# stm32f4_sd.net
KiCad netlist of a schematic drawn in EAGLE
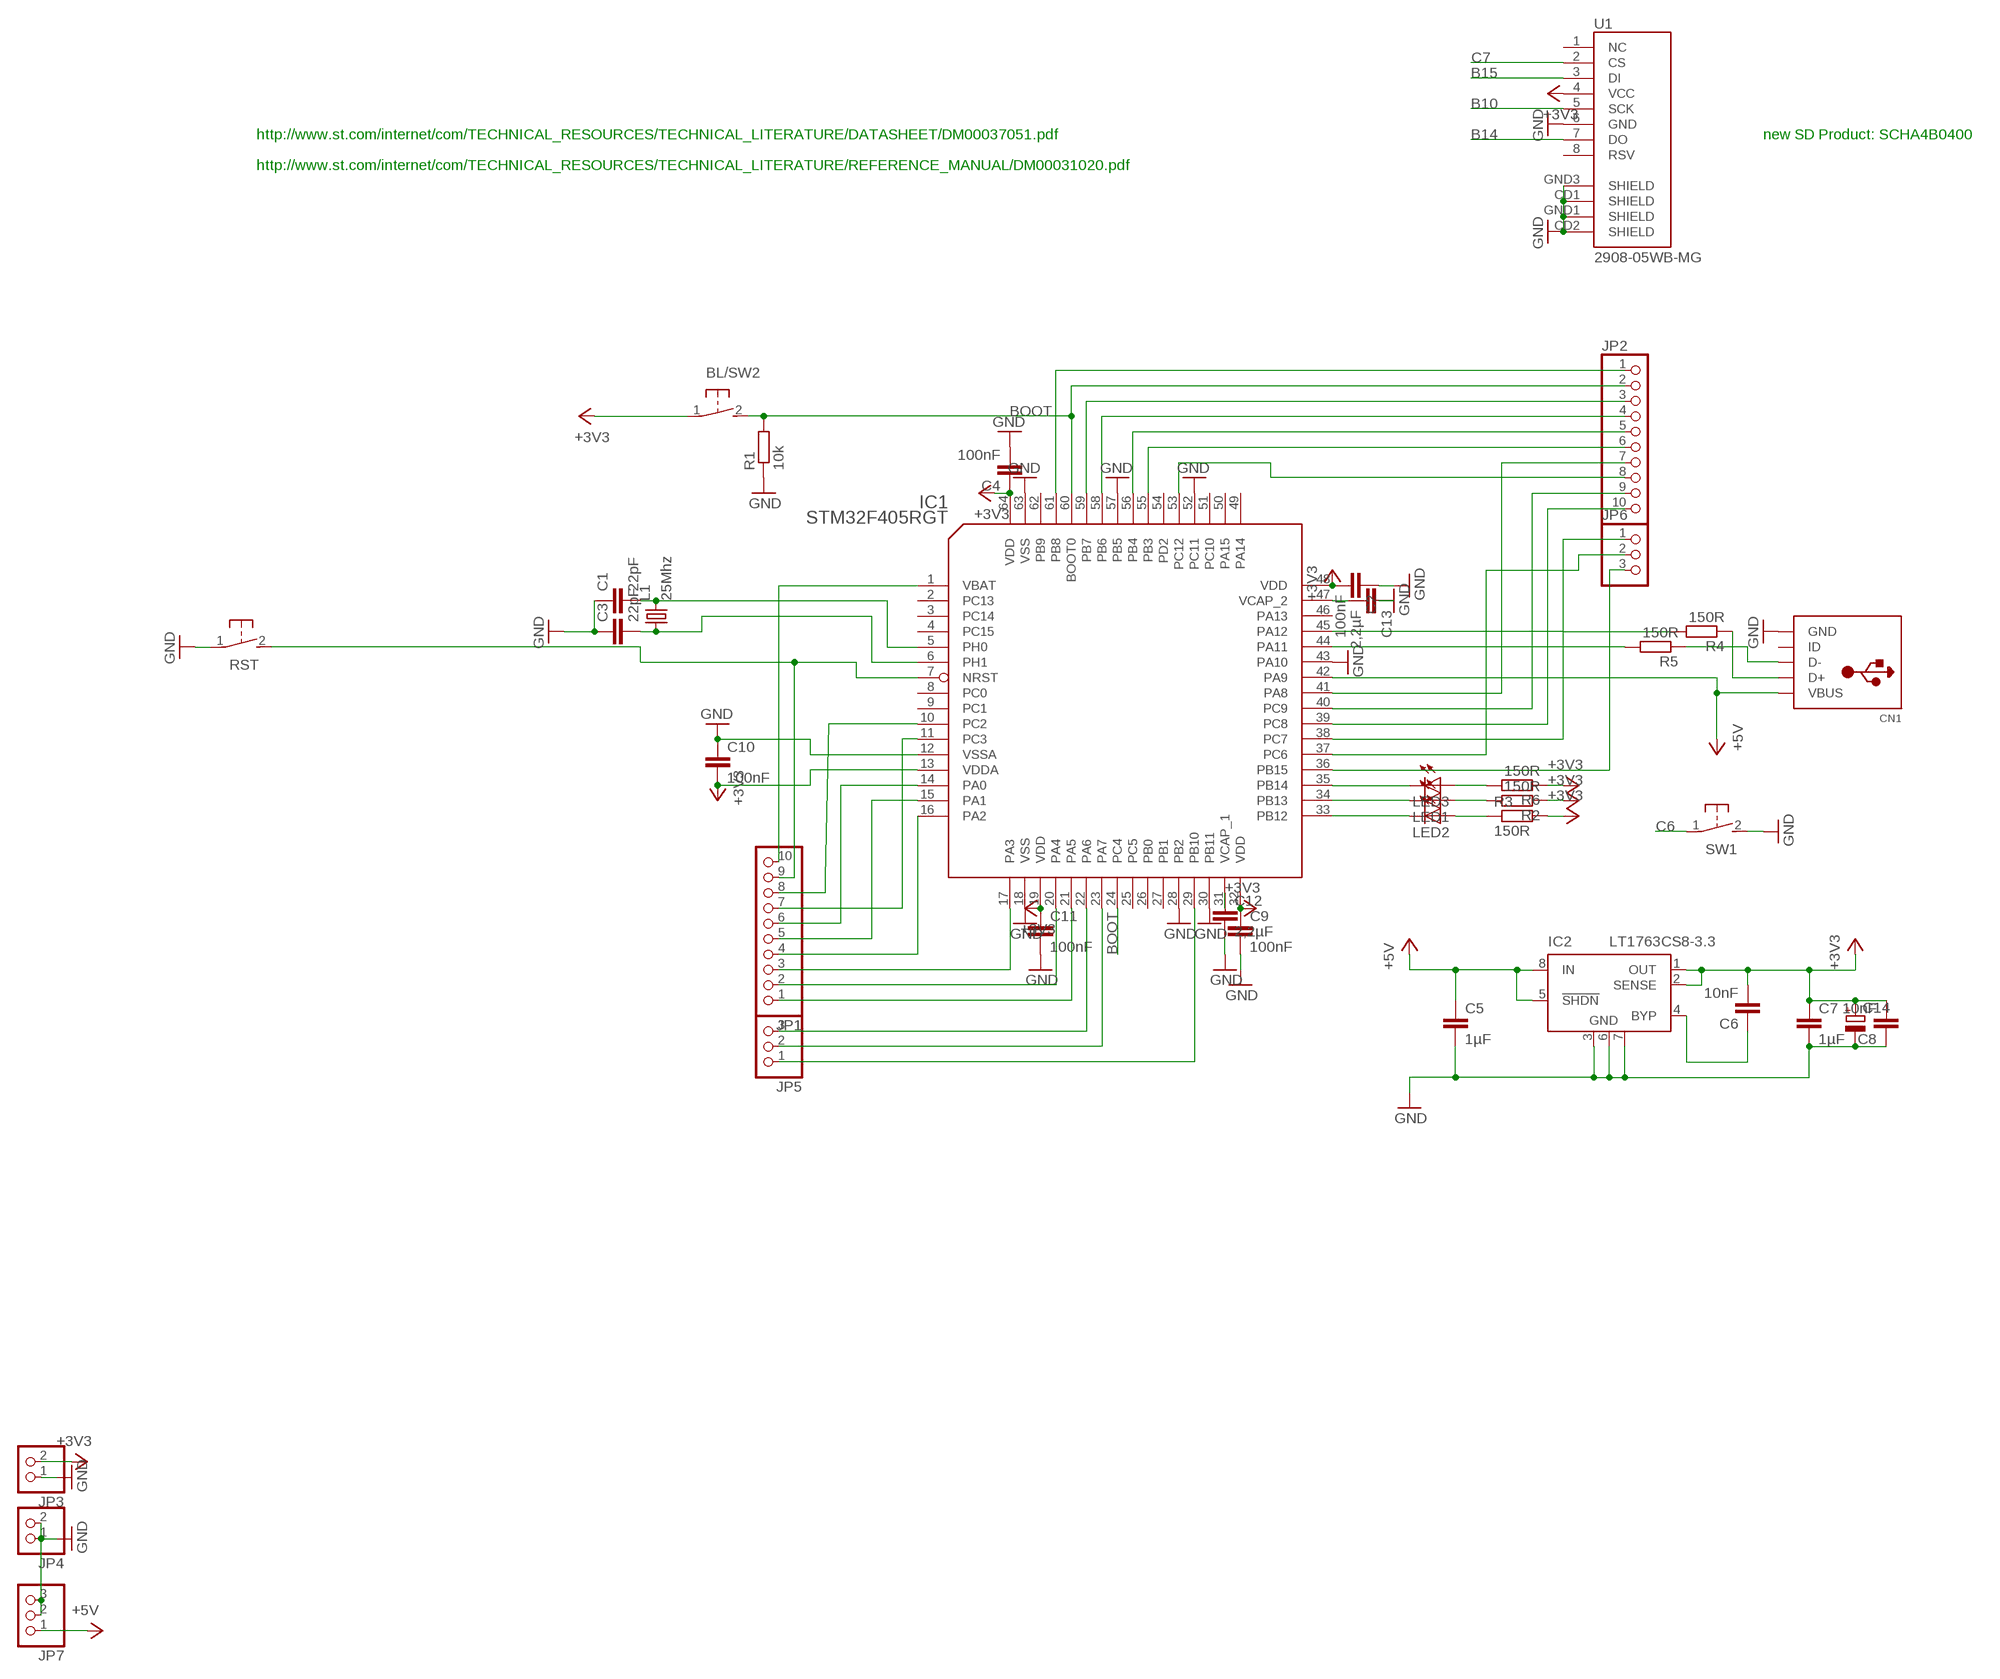
[diagram p0: schematic, sheet 1]

(export (version "E")
  (design (tool "Eeschema 10.0.6"))
  (components
    (comp (ref "BL/SW2")
      (value "SWITCH_MCTAEF")
      (footprint "eagle-import:SWITCH_MCTAEF")
      (libsource (lib "eagle-import") (part "SWITCH_MCTAEF"))
    )
    (comp (ref "C1")
      (value "22pF")
      (footprint "eagle-import:C0402")
      (libsource (lib "eagle-import") (part "C-EUC0402"))
    )
    (comp (ref "C2")
      (value "100nF")
      (footprint "eagle-import:C0402")
      (libsource (lib "eagle-import") (part "C-EUC0402"))
    )
    (comp (ref "C3")
      (value "22pF")
      (footprint "eagle-import:C0402")
      (libsource (lib "eagle-import") (part "C-EUC0402"))
    )
    (comp (ref "C4")
      (value "100nF")
      (footprint "eagle-import:C0402")
      (libsource (lib "eagle-import") (part "C-EUC0402"))
    )
    (comp (ref "C5")
      (value "1µF")
      (footprint "eagle-import:0805")
      (libsource (lib "eagle-import") (part "CAP0805"))
    )
    (comp (ref "C6")
      (value "10nF")
      (footprint "eagle-import:C0402")
      (libsource (lib "eagle-import") (part "C-EUC0402"))
    )
    (comp (ref "C7")
      (value "1µF")
      (footprint "eagle-import:0805")
      (libsource (lib "eagle-import") (part "CAP0805"))
    )
    (comp (ref "C8")
      (value "10nF")
      (footprint "eagle-import:C0402")
      (libsource (lib "eagle-import") (part "C-EUC0402"))
    )
    (comp (ref "C9")
      (value "100nF")
      (footprint "eagle-import:C0402")
      (libsource (lib "eagle-import") (part "C-EUC0402"))
    )
    (comp (ref "C10")
      (value "100nF")
      (footprint "eagle-import:C0402")
      (libsource (lib "eagle-import") (part "C-EUC0402"))
    )
    (comp (ref "C11")
      (value "100nF")
      (footprint "eagle-import:C0402")
      (libsource (lib "eagle-import") (part "C-EUC0402"))
    )
    (comp (ref "C12")
      (value "2,2µF")
      (footprint "eagle-import:0805")
      (libsource (lib "eagle-import") (part "CAP0805"))
    )
    (comp (ref "C13")
      (value "2,2µF")
      (footprint "eagle-import:0805")
      (libsource (lib "eagle-import") (part "CAP0805"))
    )
    (comp (ref "C14")
      (value "CPOL-EUSMCA")
      (footprint "eagle-import:SMC_A")
      (libsource (lib "eagle-import") (part "CPOL-EUSMCA"))
    )
    (comp (ref "CN1")
      (value "USBMINIB")
      (footprint "eagle-import:USB-MINIB")
      (libsource (lib "eagle-import") (part "USBMINIB"))
    )
    (comp (ref "IC1")
      (value "STM32F405RGT")
      (footprint "eagle-import:LQFP64")
      (libsource (lib "eagle-import") (part "STM32F405RTG"))
    )
    (comp (ref "IC2")
      (value "LT1763CS8-3.3")
      (footprint "eagle-import:SOIC8")
      (libsource (lib "eagle-import") (part "LT1763CS8-3.3"))
    )
    (comp (ref "JP1")
      (value "PINHD-1X10_2.54")
      (footprint "eagle-import:1X10")
      (libsource (lib "eagle-import") (part "PINHD-1X10_2.54"))
    )
    (comp (ref "JP2")
      (value "PINHD-1X10_2.54")
      (footprint "eagle-import:1X10")
      (libsource (lib "eagle-import") (part "PINHD-1X10_2.54"))
    )
    (comp (ref "JP3")
      (value "PINHD-1X02_2.54")
      (footprint "eagle-import:1X02")
      (libsource (lib "eagle-import") (part "PINHD-1X02_2.54"))
    )
    (comp (ref "JP4")
      (value "PINHD-1X02_2.54")
      (footprint "eagle-import:1X02")
      (libsource (lib "eagle-import") (part "PINHD-1X02_2.54"))
    )
    (comp (ref "JP5")
      (value "PINHD-1X03_2.54")
      (footprint "eagle-import:1X03")
      (libsource (lib "eagle-import") (part "PINHD-1X03_2.54"))
    )
    (comp (ref "JP6")
      (value "PINHD-1X03_2.54")
      (footprint "eagle-import:1X03")
      (libsource (lib "eagle-import") (part "PINHD-1X03_2.54"))
    )
    (comp (ref "JP7")
      (value "PINHD-1X03_2.54")
      (footprint "eagle-import:1X03")
      (libsource (lib "eagle-import") (part "PINHD-1X03_2.54"))
    )
    (comp (ref "L1")
      (value "25Mhz")
      (footprint "eagle-import:X22")
      (libsource (lib "eagle-import") (part "X22-OSCILLATOR"))
    )
    (comp (ref "LED1")
      (value "LED0603")
      (footprint "eagle-import:LED-0603")
      (libsource (lib "eagle-import") (part "LED0603"))
    )
    (comp (ref "LED2")
      (value "LED0603")
      (footprint "eagle-import:LED-0603")
      (libsource (lib "eagle-import") (part "LED0603"))
    )
    (comp (ref "LED3")
      (value "LED0603")
      (footprint "eagle-import:LED-0603")
      (libsource (lib "eagle-import") (part "LED0603"))
    )
    (comp (ref "R1")
      (value "10k")
      (footprint "eagle-import:R0402")
      (libsource (lib "eagle-import") (part "R-EU_R0402"))
    )
    (comp (ref "R2")
      (value "150R")
      (footprint "eagle-import:R0402")
      (libsource (lib "eagle-import") (part "R-EU_R0402"))
    )
    (comp (ref "R3")
      (value "150R")
      (footprint "eagle-import:R0402")
      (libsource (lib "eagle-import") (part "R-EU_R0402"))
    )
    (comp (ref "R4")
      (value "150R")
      (footprint "eagle-import:R0402")
      (libsource (lib "eagle-import") (part "R-EU_R0402"))
    )
    (comp (ref "R5")
      (value "150R")
      (footprint "eagle-import:R0402")
      (libsource (lib "eagle-import") (part "R-EU_R0402"))
    )
    (comp (ref "R6")
      (value "150R")
      (footprint "eagle-import:R0402")
      (libsource (lib "eagle-import") (part "R-EU_R0402"))
    )
    (comp (ref "RST")
      (value "SWITCH_MCTAEF")
      (footprint "eagle-import:SWITCH_MCTAEF")
      (libsource (lib "eagle-import") (part "SWITCH_MCTAEF"))
    )
    (comp (ref "SW1")
      (value "SWITCH_MCTAEF")
      (footprint "eagle-import:SWITCH_MCTAEF")
      (libsource (lib "eagle-import") (part "SWITCH_MCTAEF"))
    )
    (comp (ref "U1")
      (value "2908-05WB-MG")
      (footprint "eagle-import:MICRO-SD-SOCKET-PP")
      (libsource (lib "eagle-import") (part "USD-SOCKETNEW"))
    )
  )
  (nets
    (net (code "1") (name "+3V3") (class "Default")
      (node (ref "BL/SW2") (pin "1") (pinfunction "1_1") (pintype "passive"))
      (node (ref "C10") (pin "2") (pinfunction "2_2") (pintype "passive"))
      (node (ref "C11") (pin "1") (pinfunction "1_1") (pintype "passive"))
      (node (ref "C14") (pin "+") (pinfunction "+_+") (pintype "passive"))
      (node (ref "C2") (pin "2") (pinfunction "2_2") (pintype "passive"))
      (node (ref "C4") (pin "1") (pinfunction "1_1") (pintype "passive"))
      (node (ref "C6") (pin "2") (pinfunction "2_2") (pintype "passive"))
      (node (ref "C7") (pin "1") (pinfunction "1_1") (pintype "passive"))
      (node (ref "C8") (pin "2") (pinfunction "2_2") (pintype "passive"))
      (node (ref "C9") (pin "1") (pinfunction "1_1") (pintype "passive"))
      (node (ref "IC1") (pin "13") (pinfunction "VDDA_13") (pintype "power_in"))
      (node (ref "IC1") (pin "19") (pinfunction "VDD_19") (pintype "power_in"))
      (node (ref "IC1") (pin "32") (pinfunction "VDD_32") (pintype "power_in"))
      (node (ref "IC1") (pin "48") (pinfunction "VDD_48") (pintype "power_in"))
      (node (ref "IC1") (pin "64") (pinfunction "VDD_64") (pintype "power_in"))
      (node (ref "IC2") (pin "1") (pinfunction "OUT_1") (pintype "passive"))
      (node (ref "IC2") (pin "2") (pinfunction "SENSE_2") (pintype "input"))
      (node (ref "JP3") (pin "2") (pinfunction "2_2") (pintype "passive"))
      (node (ref "R2") (pin "1") (pinfunction "1_1") (pintype "passive"))
      (node (ref "R3") (pin "2") (pinfunction "2_2") (pintype "passive"))
      (node (ref "R6") (pin "1") (pinfunction "1_1") (pintype "passive"))
      (node (ref "U1") (pin "4") (pinfunction "VCC_4") (pintype "bidirectional"))
    )
    (net (code "2") (name "+5V") (class "Default")
      (node (ref "C5") (pin "1") (pinfunction "1_1") (pintype "passive"))
      (node (ref "CN1") (pin "VBUS") (pinfunction "VBUS_VBUS") (pintype "power_in"))
      (node (ref "IC1") (pin "42") (pinfunction "PA9_42") (pintype "bidirectional"))
      (node (ref "IC2") (pin "5") (pinfunction "~{SHDN}_5") (pintype "input"))
      (node (ref "IC2") (pin "8") (pinfunction "IN_8") (pintype "input"))
      (node (ref "JP7") (pin "1") (pinfunction "1_1") (pintype "passive"))
    )
    (net (code "3") (name "/B10") (class "Default")
      (node (ref "IC1") (pin "29") (pinfunction "PB10_29") (pintype "bidirectional"))
      (node (ref "JP5") (pin "1") (pinfunction "1_1") (pintype "passive"))
      (node (ref "U1") (pin "5") (pinfunction "SCK_5") (pintype "bidirectional"))
    )
    (net (code "4") (name "/B14") (class "Default")
      (node (ref "IC1") (pin "36") (pinfunction "PB15_36") (pintype "bidirectional"))
      (node (ref "JP6") (pin "3") (pinfunction "3_3") (pintype "passive"))
      (node (ref "U1") (pin "7") (pinfunction "DO_7") (pintype "bidirectional"))
    )
    (net (code "5") (name "/B15") (class "Default")
      (node (ref "IC1") (pin "37") (pinfunction "PC6_37") (pintype "bidirectional"))
      (node (ref "JP6") (pin "2") (pinfunction "2_2") (pintype "passive"))
      (node (ref "U1") (pin "3") (pinfunction "DI_3") (pintype "bidirectional"))
    )
    (net (code "6") (name "/BOOT") (class "Default")
      (node (ref "BL/SW2") (pin "2") (pinfunction "2_2") (pintype "passive"))
      (node (ref "IC1") (pin "24") (pinfunction "PC4_24") (pintype "bidirectional"))
      (node (ref "IC1") (pin "60") (pinfunction "BOOT0_60") (pintype "bidirectional"))
      (node (ref "JP2") (pin "2") (pinfunction "2_2") (pintype "passive"))
      (node (ref "R1") (pin "2") (pinfunction "2_2") (pintype "passive"))
    )
    (net (code "7") (name "/C6") (class "Default")
      (node (ref "IC1") (pin "38") (pinfunction "PC7_38") (pintype "bidirectional"))
      (node (ref "JP6") (pin "1") (pinfunction "1_1") (pintype "passive"))
      (node (ref "SW1") (pin "1") (pinfunction "1_1") (pintype "passive"))
    )
    (net (code "8") (name "/C7") (class "Default")
      (node (ref "IC1") (pin "39") (pinfunction "PC8_39") (pintype "bidirectional"))
      (node (ref "JP2") (pin "10") (pinfunction "10_10") (pintype "passive"))
      (node (ref "U1") (pin "2") (pinfunction "CS_2") (pintype "bidirectional"))
    )
    (net (code "9") (name "GND") (class "Default")
      (node (ref "C1") (pin "1") (pinfunction "1_1") (pintype "passive"))
      (node (ref "C10") (pin "1") (pinfunction "1_1") (pintype "passive"))
      (node (ref "C11") (pin "2") (pinfunction "2_2") (pintype "passive"))
      (node (ref "C12") (pin "2") (pinfunction "2_2") (pintype "passive"))
      (node (ref "C13") (pin "1") (pinfunction "1_1") (pintype "passive"))
      (node (ref "C14") (pin "-") (pinfunction "-_-") (pintype "passive"))
      (node (ref "C2") (pin "1") (pinfunction "1_1") (pintype "passive"))
      (node (ref "C3") (pin "1") (pinfunction "1_1") (pintype "passive"))
      (node (ref "C4") (pin "2") (pinfunction "2_2") (pintype "passive"))
      (node (ref "C5") (pin "2") (pinfunction "2_2") (pintype "passive"))
      (node (ref "C7") (pin "2") (pinfunction "2_2") (pintype "passive"))
      (node (ref "C8") (pin "1") (pinfunction "1_1") (pintype "passive"))
      (node (ref "C9") (pin "2") (pinfunction "2_2") (pintype "passive"))
      (node (ref "CN1") (pin "GND") (pinfunction "GND_GND") (pintype "power_in"))
      (node (ref "IC1") (pin "12") (pinfunction "VSSA_12") (pintype "power_in"))
      (node (ref "IC1") (pin "18") (pinfunction "VSS_18") (pintype "power_in"))
      (node (ref "IC1") (pin "28") (pinfunction "PB2_28") (pintype "bidirectional"))
      (node (ref "IC1") (pin "30") (pinfunction "PB11_30") (pintype "bidirectional"))
      (node (ref "IC1") (pin "43") (pinfunction "PA10_43") (pintype "bidirectional"))
      (node (ref "IC1") (pin "52") (pinfunction "PC11_52") (pintype "bidirectional"))
      (node (ref "IC1") (pin "57") (pinfunction "PB5_57") (pintype "bidirectional"))
      (node (ref "IC1") (pin "63") (pinfunction "VSS_63") (pintype "power_in"))
      (node (ref "IC2") (pin "3") (pinfunction "GND_3") (pintype "power_in"))
      (node (ref "IC2") (pin "6") (pinfunction "GND_6") (pintype "power_in"))
      (node (ref "IC2") (pin "7") (pinfunction "GND_7") (pintype "power_in"))
      (node (ref "JP3") (pin "1") (pinfunction "1_1") (pintype "passive"))
      (node (ref "JP4") (pin "1") (pinfunction "1_1") (pintype "passive"))
      (node (ref "JP4") (pin "2") (pinfunction "2_2") (pintype "passive"))
      (node (ref "JP7") (pin "2") (pinfunction "2_2") (pintype "passive"))
      (node (ref "JP7") (pin "3") (pinfunction "3_3") (pintype "passive"))
      (node (ref "R1") (pin "1") (pinfunction "1_1") (pintype "passive"))
      (node (ref "RST") (pin "1") (pinfunction "1_1") (pintype "passive"))
      (node (ref "SW1") (pin "2") (pinfunction "2_2") (pintype "passive"))
      (node (ref "U1") (pin "6") (pinfunction "GND_6") (pintype "bidirectional"))
      (node (ref "U1") (pin "CD1") (pinfunction "SHIELD_CD1") (pintype "bidirectional"))
      (node (ref "U1") (pin "CD2") (pinfunction "SHIELD_CD2") (pintype "bidirectional"))
      (node (ref "U1") (pin "GND1") (pinfunction "SHIELD_GND1") (pintype "bidirectional"))
      (node (ref "U1") (pin "GND3") (pinfunction "SHIELD_GND3") (pintype "bidirectional"))
    )
    (net (code "10") (name "Net-(CN1-PadD+)") (class "Default")
      (node (ref "CN1") (pin "D+") (pinfunction "D+_D+") (pintype "bidirectional"))
      (node (ref "R4") (pin "1") (pinfunction "1_1") (pintype "passive"))
    )
    (net (code "11") (name "Net-(CN1-PadD-)") (class "Default")
      (node (ref "CN1") (pin "D-") (pinfunction "D-_D-") (pintype "bidirectional"))
      (node (ref "R5") (pin "1") (pinfunction "1_1") (pintype "passive"))
    )
    (net (code "12") (name "Net-(IC1-NRST)") (class "Default")
      (node (ref "IC1") (pin "7") (pinfunction "NRST_7") (pintype "input"))
      (node (ref "JP1") (pin "9") (pinfunction "9_9") (pintype "passive"))
      (node (ref "RST") (pin "2") (pinfunction "2_2") (pintype "passive"))
    )
    (net (code "13") (name "Net-(IC1-PA0)") (class "Default")
      (node (ref "IC1") (pin "14") (pinfunction "PA0_14") (pintype "bidirectional"))
      (node (ref "JP1") (pin "6") (pinfunction "6_6") (pintype "passive"))
    )
    (net (code "14") (name "Net-(IC1-PA1)") (class "Default")
      (node (ref "IC1") (pin "15") (pinfunction "PA1_15") (pintype "bidirectional"))
      (node (ref "JP1") (pin "5") (pinfunction "5_5") (pintype "passive"))
    )
    (net (code "15") (name "Net-(IC1-PA2)") (class "Default")
      (node (ref "IC1") (pin "16") (pinfunction "PA2_16") (pintype "bidirectional"))
      (node (ref "JP1") (pin "4") (pinfunction "4_4") (pintype "passive"))
    )
    (net (code "16") (name "Net-(IC1-PA3)") (class "Default")
      (node (ref "IC1") (pin "17") (pinfunction "PA3_17") (pintype "bidirectional"))
      (node (ref "JP1") (pin "3") (pinfunction "3_3") (pintype "passive"))
    )
    (net (code "17") (name "Net-(IC1-PA4)") (class "Default")
      (node (ref "IC1") (pin "20") (pinfunction "PA4_20") (pintype "bidirectional"))
      (node (ref "JP1") (pin "2") (pinfunction "2_2") (pintype "passive"))
    )
    (net (code "18") (name "Net-(IC1-PA5)") (class "Default")
      (node (ref "IC1") (pin "21") (pinfunction "PA5_21") (pintype "bidirectional"))
      (node (ref "JP1") (pin "1") (pinfunction "1_1") (pintype "passive"))
    )
    (net (code "19") (name "Net-(IC1-PA6)") (class "Default")
      (node (ref "IC1") (pin "22") (pinfunction "PA6_22") (pintype "bidirectional"))
      (node (ref "JP5") (pin "3") (pinfunction "3_3") (pintype "passive"))
    )
    (net (code "20") (name "Net-(IC1-PA7)") (class "Default")
      (node (ref "IC1") (pin "23") (pinfunction "PA7_23") (pintype "bidirectional"))
      (node (ref "JP5") (pin "2") (pinfunction "2_2") (pintype "passive"))
    )
    (net (code "21") (name "Net-(IC1-PA8)") (class "Default")
      (node (ref "IC1") (pin "41") (pinfunction "PA8_41") (pintype "bidirectional"))
      (node (ref "JP2") (pin "7") (pinfunction "7_7") (pintype "passive"))
    )
    (net (code "22") (name "Net-(IC1-PA11)") (class "Default")
      (node (ref "IC1") (pin "44") (pinfunction "PA11_44") (pintype "bidirectional"))
      (node (ref "R5") (pin "2") (pinfunction "2_2") (pintype "passive"))
    )
    (net (code "23") (name "Net-(IC1-PA12)") (class "Default")
      (node (ref "IC1") (pin "45") (pinfunction "PA12_45") (pintype "bidirectional"))
      (node (ref "R4") (pin "2") (pinfunction "2_2") (pintype "passive"))
    )
    (net (code "24") (name "Net-(IC1-PB3)") (class "Default")
      (node (ref "IC1") (pin "55") (pinfunction "PB3_55") (pintype "bidirectional"))
      (node (ref "JP2") (pin "6") (pinfunction "6_6") (pintype "passive"))
    )
    (net (code "25") (name "Net-(IC1-PB4)") (class "Default")
      (node (ref "IC1") (pin "56") (pinfunction "PB4_56") (pintype "bidirectional"))
      (node (ref "JP2") (pin "5") (pinfunction "5_5") (pintype "passive"))
    )
    (net (code "26") (name "Net-(IC1-PB6)") (class "Default")
      (node (ref "IC1") (pin "58") (pinfunction "PB6_58") (pintype "bidirectional"))
      (node (ref "JP2") (pin "4") (pinfunction "4_4") (pintype "passive"))
    )
    (net (code "27") (name "Net-(IC1-PB7)") (class "Default")
      (node (ref "IC1") (pin "59") (pinfunction "PB7_59") (pintype "bidirectional"))
      (node (ref "JP2") (pin "3") (pinfunction "3_3") (pintype "passive"))
    )
    (net (code "28") (name "Net-(IC1-PB8)") (class "Default")
      (node (ref "IC1") (pin "61") (pinfunction "PB8_61") (pintype "bidirectional"))
      (node (ref "JP2") (pin "1") (pinfunction "1_1") (pintype "passive"))
    )
    (net (code "29") (name "Net-(IC1-PB12)") (class "Default")
      (node (ref "IC1") (pin "33") (pinfunction "PB12_33") (pintype "bidirectional"))
      (node (ref "LED2") (pin "C") (pinfunction "C_C") (pintype "passive"))
    )
    (net (code "30") (name "Net-(IC1-PB13)") (class "Default")
      (node (ref "IC1") (pin "34") (pinfunction "PB13_34") (pintype "bidirectional"))
      (node (ref "LED1") (pin "C") (pinfunction "C_C") (pintype "passive"))
    )
    (net (code "31") (name "Net-(IC1-PB14)") (class "Default")
      (node (ref "IC1") (pin "35") (pinfunction "PB14_35") (pintype "bidirectional"))
      (node (ref "LED3") (pin "C") (pinfunction "C_C") (pintype "passive"))
    )
    (net (code "32") (name "Net-(IC1-PC2)") (class "Default")
      (node (ref "IC1") (pin "10") (pinfunction "PC2_10") (pintype "bidirectional"))
      (node (ref "JP1") (pin "8") (pinfunction "8_8") (pintype "passive"))
    )
    (net (code "33") (name "Net-(IC1-PC3)") (class "Default")
      (node (ref "IC1") (pin "11") (pinfunction "PC3_11") (pintype "bidirectional"))
      (node (ref "JP1") (pin "7") (pinfunction "7_7") (pintype "passive"))
    )
    (net (code "34") (name "Net-(IC1-PC9)") (class "Default")
      (node (ref "IC1") (pin "40") (pinfunction "PC9_40") (pintype "bidirectional"))
      (node (ref "JP2") (pin "9") (pinfunction "9_9") (pintype "passive"))
    )
    (net (code "35") (name "Net-(IC1-PC12)") (class "Default")
      (node (ref "IC1") (pin "53") (pinfunction "PC12_53") (pintype "bidirectional"))
      (node (ref "JP2") (pin "8") (pinfunction "8_8") (pintype "passive"))
    )
    (net (code "36") (name "Net-(IC1-PH0)") (class "Default")
      (node (ref "C1") (pin "2") (pinfunction "2_2") (pintype "passive"))
      (node (ref "IC1") (pin "5") (pinfunction "PH0_5") (pintype "bidirectional"))
      (node (ref "L1") (pin "3") (pinfunction "2_3") (pintype "passive"))
    )
    (net (code "37") (name "Net-(IC1-PH1)") (class "Default")
      (node (ref "C3") (pin "2") (pinfunction "2_2") (pintype "passive"))
      (node (ref "IC1") (pin "6") (pinfunction "PH1_6") (pintype "bidirectional"))
      (node (ref "L1") (pin "1") (pinfunction "1_1") (pintype "passive"))
    )
    (net (code "38") (name "Net-(IC1-VBAT)") (class "Default")
      (node (ref "IC1") (pin "1") (pinfunction "VBAT_1") (pintype "power_in"))
      (node (ref "JP1") (pin "10") (pinfunction "10_10") (pintype "passive"))
    )
    (net (code "39") (name "Net-(IC1-VCAP_1)") (class "Default")
      (node (ref "C12") (pin "1") (pinfunction "1_1") (pintype "passive"))
      (node (ref "IC1") (pin "31") (pinfunction "VCAP_1_31") (pintype "passive"))
    )
    (net (code "40") (name "Net-(IC1-VCAP_2)") (class "Default")
      (node (ref "C13") (pin "2") (pinfunction "2_2") (pintype "passive"))
      (node (ref "IC1") (pin "47") (pinfunction "VCAP_2_47") (pintype "passive"))
    )
    (net (code "41") (name "Net-(IC2-BYP)") (class "Default")
      (node (ref "C6") (pin "1") (pinfunction "1_1") (pintype "passive"))
      (node (ref "IC2") (pin "4") (pinfunction "BYP_4") (pintype "input"))
    )
    (net (code "42") (name "Net-(LED1-PadA)") (class "Default")
      (node (ref "LED1") (pin "A") (pinfunction "A_A") (pintype "passive"))
      (node (ref "R2") (pin "2") (pinfunction "2_2") (pintype "passive"))
    )
    (net (code "43") (name "Net-(LED2-PadA)") (class "Default")
      (node (ref "LED2") (pin "A") (pinfunction "A_A") (pintype "passive"))
      (node (ref "R3") (pin "1") (pinfunction "1_1") (pintype "passive"))
    )
    (net (code "44") (name "Net-(LED3-PadA)") (class "Default")
      (node (ref "LED3") (pin "A") (pinfunction "A_A") (pintype "passive"))
      (node (ref "R6") (pin "2") (pinfunction "2_2") (pintype "passive"))
    )
    (net (code "45") (name "unconnected-(CN1-PadID)") (class "Default")
      (node (ref "CN1") (pin "ID") (pinfunction "ID_ID") (pintype "bidirectional"))
    )
    (net (code "46") (name "unconnected-(IC1-PA13-Pad46)") (class "Default")
      (node (ref "IC1") (pin "46") (pinfunction "PA13_46") (pintype "bidirectional"))
    )
    (net (code "47") (name "unconnected-(IC1-PA14-Pad49)") (class "Default")
      (node (ref "IC1") (pin "49") (pinfunction "PA14_49") (pintype "bidirectional"))
    )
    (net (code "48") (name "unconnected-(IC1-PA15-Pad50)") (class "Default")
      (node (ref "IC1") (pin "50") (pinfunction "PA15_50") (pintype "bidirectional"))
    )
    (net (code "49") (name "unconnected-(IC1-PB0-Pad26)") (class "Default")
      (node (ref "IC1") (pin "26") (pinfunction "PB0_26") (pintype "bidirectional"))
    )
    (net (code "50") (name "unconnected-(IC1-PB1-Pad27)") (class "Default")
      (node (ref "IC1") (pin "27") (pinfunction "PB1_27") (pintype "bidirectional"))
    )
    (net (code "51") (name "unconnected-(IC1-PB9-Pad62)") (class "Default")
      (node (ref "IC1") (pin "62") (pinfunction "PB9_62") (pintype "bidirectional"))
    )
    (net (code "52") (name "unconnected-(IC1-PC0-Pad8)") (class "Default")
      (node (ref "IC1") (pin "8") (pinfunction "PC0_8") (pintype "bidirectional"))
    )
    (net (code "53") (name "unconnected-(IC1-PC1-Pad9)") (class "Default")
      (node (ref "IC1") (pin "9") (pinfunction "PC1_9") (pintype "bidirectional"))
    )
    (net (code "54") (name "unconnected-(IC1-PC5-Pad25)") (class "Default")
      (node (ref "IC1") (pin "25") (pinfunction "PC5_25") (pintype "bidirectional"))
    )
    (net (code "55") (name "unconnected-(IC1-PC10-Pad51)") (class "Default")
      (node (ref "IC1") (pin "51") (pinfunction "PC10_51") (pintype "bidirectional"))
    )
    (net (code "56") (name "unconnected-(IC1-PC13-Pad2)") (class "Default")
      (node (ref "IC1") (pin "2") (pinfunction "PC13_2") (pintype "bidirectional"))
    )
    (net (code "57") (name "unconnected-(IC1-PC14-Pad3)") (class "Default")
      (node (ref "IC1") (pin "3") (pinfunction "PC14_3") (pintype "bidirectional"))
    )
    (net (code "58") (name "unconnected-(IC1-PC15-Pad4)") (class "Default")
      (node (ref "IC1") (pin "4") (pinfunction "PC15_4") (pintype "bidirectional"))
    )
    (net (code "59") (name "unconnected-(IC1-PD2-Pad54)") (class "Default")
      (node (ref "IC1") (pin "54") (pinfunction "PD2_54") (pintype "bidirectional"))
    )
    (net (code "60") (name "unconnected-(U1-NC-Pad1)") (class "Default")
      (node (ref "U1") (pin "1") (pinfunction "NC_1") (pintype "bidirectional"))
    )
    (net (code "61") (name "unconnected-(U1-RSV-Pad8)") (class "Default")
      (node (ref "U1") (pin "8") (pinfunction "RSV_8") (pintype "bidirectional"))
    )
  )
)
